# battery-charger.net
KiCad netlist of a schematic drawn in EAGLE
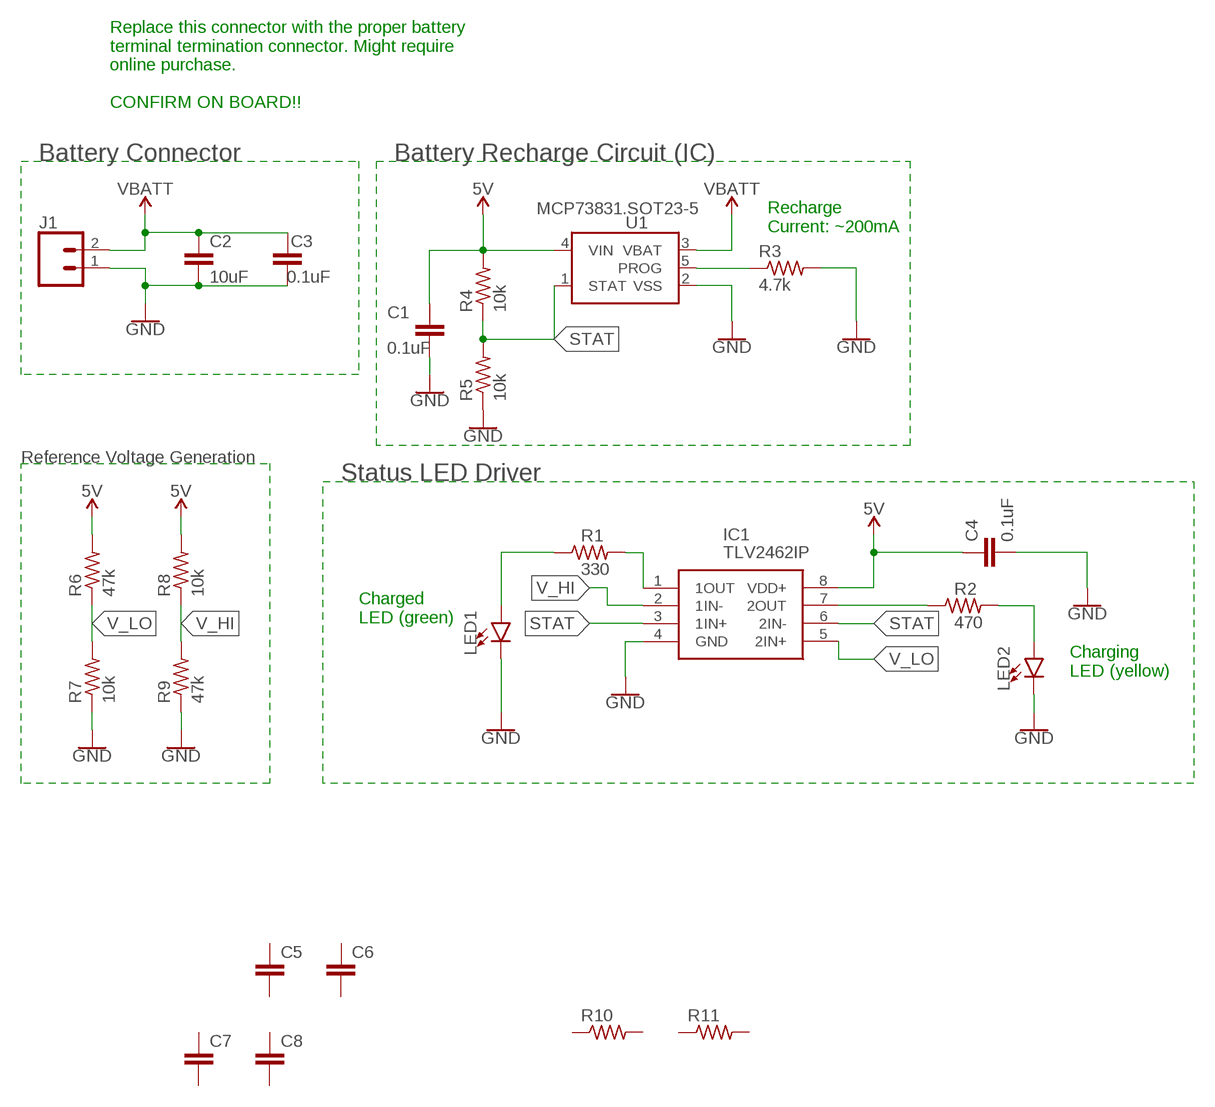
[diagram p0: schematic, sheet 1]

(export (version "E")
  (design (tool "Eeschema 10.0.6"))
  (components
    (comp (ref "C1")
      (value "0.1uF")
      (footprint "eagle-import:C0603")
      (libsource (lib "eagle-import") (part "CAPACITOR0603"))
    )
    (comp (ref "C2")
      (value "10uF")
      (footprint "eagle-import:C0603")
      (libsource (lib "eagle-import") (part "CAPACITOR0603"))
    )
    (comp (ref "C3")
      (value "0.1uF")
      (footprint "eagle-import:C0603")
      (libsource (lib "eagle-import") (part "CAPACITOR0603"))
    )
    (comp (ref "C4")
      (value "0.1uF")
      (footprint "eagle-import:C0603")
      (libsource (lib "eagle-import") (part "CAPACITOR0603"))
    )
    (comp (ref "C5")
      (value "CAPACITOR0603")
      (footprint "eagle-import:C0603")
      (libsource (lib "eagle-import") (part "CAPACITOR0603"))
    )
    (comp (ref "C6")
      (value "CAPACITOR0603")
      (footprint "eagle-import:C0603")
      (libsource (lib "eagle-import") (part "CAPACITOR0603"))
    )
    (comp (ref "C7")
      (value "CAPACITOR0603")
      (footprint "eagle-import:C0603")
      (libsource (lib "eagle-import") (part "CAPACITOR0603"))
    )
    (comp (ref "C8")
      (value "CAPACITOR0603")
      (footprint "eagle-import:C0603")
      (libsource (lib "eagle-import") (part "CAPACITOR0603"))
    )
    (comp (ref "IC1")
      (value "TLV2462IP")
      (footprint "eagle-import:DIP794W53P254L959H508Q8N")
      (fields (field (name "MOUSER_PART_NUMBER") "595-TLV2462IP"))
      (libsource (lib "eagle-import") (part "TLV2462IP"))
    )
    (comp (ref "J1")
      (value "CONN_02PTH3")
      (footprint "eagle-import:1X02_LONGPADS")
      (libsource (lib "eagle-import") (part "CONN_02PTH3"))
    )
    (comp (ref "LED1")
      (value "LED0603")
      (footprint "eagle-import:LED-0603")
      (libsource (lib "eagle-import") (part "LED0603"))
    )
    (comp (ref "LED2")
      (value "LED0603")
      (footprint "eagle-import:LED-0603")
      (libsource (lib "eagle-import") (part "LED0603"))
    )
    (comp (ref "R1")
      (value "330")
      (footprint "eagle-import:R0603")
      (libsource (lib "eagle-import") (part "RESISTOR0603"))
    )
    (comp (ref "R2")
      (value "470")
      (footprint "eagle-import:R0603")
      (libsource (lib "eagle-import") (part "RESISTOR0603"))
    )
    (comp (ref "R3")
      (value "4.7k")
      (footprint "eagle-import:R0603")
      (libsource (lib "eagle-import") (part "RESISTOR0603"))
    )
    (comp (ref "R4")
      (value "10k")
      (footprint "eagle-import:R0603")
      (libsource (lib "eagle-import") (part "RESISTOR0603"))
    )
    (comp (ref "R5")
      (value "10k")
      (footprint "eagle-import:R0603")
      (libsource (lib "eagle-import") (part "RESISTOR0603"))
    )
    (comp (ref "R6")
      (value "47k")
      (footprint "eagle-import:R0603")
      (libsource (lib "eagle-import") (part "RESISTOR0603"))
    )
    (comp (ref "R7")
      (value "10k")
      (footprint "eagle-import:R0603")
      (libsource (lib "eagle-import") (part "RESISTOR0603"))
    )
    (comp (ref "R8")
      (value "10k")
      (footprint "eagle-import:R0603")
      (libsource (lib "eagle-import") (part "RESISTOR0603"))
    )
    (comp (ref "R9")
      (value "47k")
      (footprint "eagle-import:R0603")
      (libsource (lib "eagle-import") (part "RESISTOR0603"))
    )
    (comp (ref "R10")
      (value "RESISTOR0603")
      (footprint "eagle-import:R0603")
      (libsource (lib "eagle-import") (part "RESISTOR0603"))
    )
    (comp (ref "R11")
      (value "RESISTOR0603")
      (footprint "eagle-import:R0603")
      (libsource (lib "eagle-import") (part "RESISTOR0603"))
    )
    (comp (ref "U1")
      (value "MCP73831.SOT23-5")
      (footprint "eagle-import:SOT23-5")
      (libsource (lib "eagle-import") (part "MCP73831.SOT23-5"))
    )
  )
  (nets
    (net (code "1") (name "5V") (class "Default")
      (node (ref "C1") (pin "2") (pinfunction "2_2") (pintype "passive"))
      (node (ref "C4") (pin "1") (pinfunction "1_1") (pintype "passive"))
      (node (ref "IC1") (pin "8") (pinfunction "VDD+_8") (pintype "bidirectional"))
      (node (ref "R4") (pin "2") (pinfunction "2_2") (pintype "passive"))
      (node (ref "R6") (pin "2") (pinfunction "2_2") (pintype "passive"))
      (node (ref "R8") (pin "2") (pinfunction "2_2") (pintype "passive"))
      (node (ref "U1") (pin "4") (pinfunction "VIN_4") (pintype "power_in"))
    )
    (net (code "2") (name "GND") (class "Default")
      (node (ref "C1") (pin "1") (pinfunction "1_1") (pintype "passive"))
      (node (ref "C2") (pin "2") (pinfunction "2_2") (pintype "passive"))
      (node (ref "C3") (pin "2") (pinfunction "2_2") (pintype "passive"))
      (node (ref "C4") (pin "2") (pinfunction "2_2") (pintype "passive"))
      (node (ref "IC1") (pin "4") (pinfunction "GND_4") (pintype "bidirectional"))
      (node (ref "J1") (pin "1") (pinfunction "1_1") (pintype "passive"))
      (node (ref "LED1") (pin "C") (pinfunction "C_C") (pintype "passive"))
      (node (ref "LED2") (pin "C") (pinfunction "C_C") (pintype "passive"))
      (node (ref "R3") (pin "2") (pinfunction "2_2") (pintype "passive"))
      (node (ref "R5") (pin "1") (pinfunction "1_1") (pintype "passive"))
      (node (ref "R7") (pin "1") (pinfunction "1_1") (pintype "passive"))
      (node (ref "R9") (pin "1") (pinfunction "1_1") (pintype "passive"))
      (node (ref "U1") (pin "2") (pinfunction "VSS_2") (pintype "power_in"))
    )
    (net (code "3") (name "Net-(IC1-1OUT)") (class "Default")
      (node (ref "IC1") (pin "1") (pinfunction "1OUT_1") (pintype "bidirectional"))
      (node (ref "R1") (pin "2") (pinfunction "2_2") (pintype "passive"))
    )
    (net (code "4") (name "Net-(IC1-2OUT)") (class "Default")
      (node (ref "IC1") (pin "7") (pinfunction "2OUT_7") (pintype "bidirectional"))
      (node (ref "R2") (pin "1") (pinfunction "1_1") (pintype "passive"))
    )
    (net (code "5") (name "Net-(LED1-PadA)") (class "Default")
      (node (ref "LED1") (pin "A") (pinfunction "A_A") (pintype "passive"))
      (node (ref "R1") (pin "1") (pinfunction "1_1") (pintype "passive"))
    )
    (net (code "6") (name "Net-(LED2-PadA)") (class "Default")
      (node (ref "LED2") (pin "A") (pinfunction "A_A") (pintype "passive"))
      (node (ref "R2") (pin "2") (pinfunction "2_2") (pintype "passive"))
    )
    (net (code "7") (name "Net-(U1-PROG)") (class "Default")
      (node (ref "R3") (pin "1") (pinfunction "1_1") (pintype "passive"))
      (node (ref "U1") (pin "5") (pinfunction "PROG_5") (pintype "input"))
    )
    (net (code "8") (name "STAT") (class "Default")
      (node (ref "IC1") (pin "3") (pinfunction "1IN+_3") (pintype "bidirectional"))
      (node (ref "IC1") (pin "6") (pinfunction "2IN-_6") (pintype "bidirectional"))
      (node (ref "R4") (pin "1") (pinfunction "1_1") (pintype "passive"))
      (node (ref "R5") (pin "2") (pinfunction "2_2") (pintype "passive"))
      (node (ref "U1") (pin "1") (pinfunction "STAT_1") (pintype "output"))
    )
    (net (code "9") (name "VBATT") (class "Default")
      (node (ref "C2") (pin "1") (pinfunction "1_1") (pintype "passive"))
      (node (ref "C3") (pin "1") (pinfunction "1_1") (pintype "passive"))
      (node (ref "J1") (pin "2") (pinfunction "2_2") (pintype "passive"))
      (node (ref "U1") (pin "3") (pinfunction "VBAT_3") (pintype "power_in"))
    )
    (net (code "10") (name "V_HI") (class "Default")
      (node (ref "IC1") (pin "2") (pinfunction "1IN-_2") (pintype "bidirectional"))
      (node (ref "R8") (pin "1") (pinfunction "1_1") (pintype "passive"))
      (node (ref "R9") (pin "2") (pinfunction "2_2") (pintype "passive"))
    )
    (net (code "11") (name "V_LO") (class "Default")
      (node (ref "IC1") (pin "5") (pinfunction "2IN+_5") (pintype "bidirectional"))
      (node (ref "R6") (pin "1") (pinfunction "1_1") (pintype "passive"))
      (node (ref "R7") (pin "2") (pinfunction "2_2") (pintype "passive"))
    )
    (net (code "12") (name "unconnected-(C5-Pad1)") (class "Default")
      (node (ref "C5") (pin "1") (pinfunction "1_1") (pintype "passive"))
    )
    (net (code "13") (name "unconnected-(C5-Pad2)") (class "Default")
      (node (ref "C5") (pin "2") (pinfunction "2_2") (pintype "passive"))
    )
    (net (code "14") (name "unconnected-(C6-Pad1)") (class "Default")
      (node (ref "C6") (pin "1") (pinfunction "1_1") (pintype "passive"))
    )
    (net (code "15") (name "unconnected-(C6-Pad2)") (class "Default")
      (node (ref "C6") (pin "2") (pinfunction "2_2") (pintype "passive"))
    )
    (net (code "16") (name "unconnected-(C7-Pad1)") (class "Default")
      (node (ref "C7") (pin "1") (pinfunction "1_1") (pintype "passive"))
    )
    (net (code "17") (name "unconnected-(C7-Pad2)") (class "Default")
      (node (ref "C7") (pin "2") (pinfunction "2_2") (pintype "passive"))
    )
    (net (code "18") (name "unconnected-(C8-Pad1)") (class "Default")
      (node (ref "C8") (pin "1") (pinfunction "1_1") (pintype "passive"))
    )
    (net (code "19") (name "unconnected-(C8-Pad2)") (class "Default")
      (node (ref "C8") (pin "2") (pinfunction "2_2") (pintype "passive"))
    )
    (net (code "20") (name "unconnected-(R10-Pad1)") (class "Default")
      (node (ref "R10") (pin "1") (pinfunction "1_1") (pintype "passive"))
    )
    (net (code "21") (name "unconnected-(R10-Pad2)") (class "Default")
      (node (ref "R10") (pin "2") (pinfunction "2_2") (pintype "passive"))
    )
    (net (code "22") (name "unconnected-(R11-Pad1)") (class "Default")
      (node (ref "R11") (pin "1") (pinfunction "1_1") (pintype "passive"))
    )
    (net (code "23") (name "unconnected-(R11-Pad2)") (class "Default")
      (node (ref "R11") (pin "2") (pinfunction "2_2") (pintype "passive"))
    )
  )
)
